# LAB-DEB429.net
KiCad netlist of a schematic drawn in EAGLE
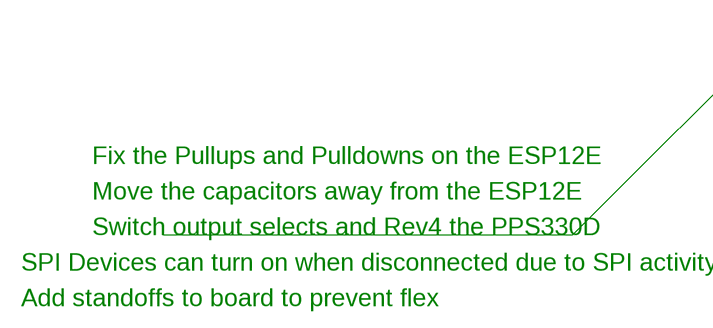
[diagram p0: schematic, sheet 1, part 1 of 2]
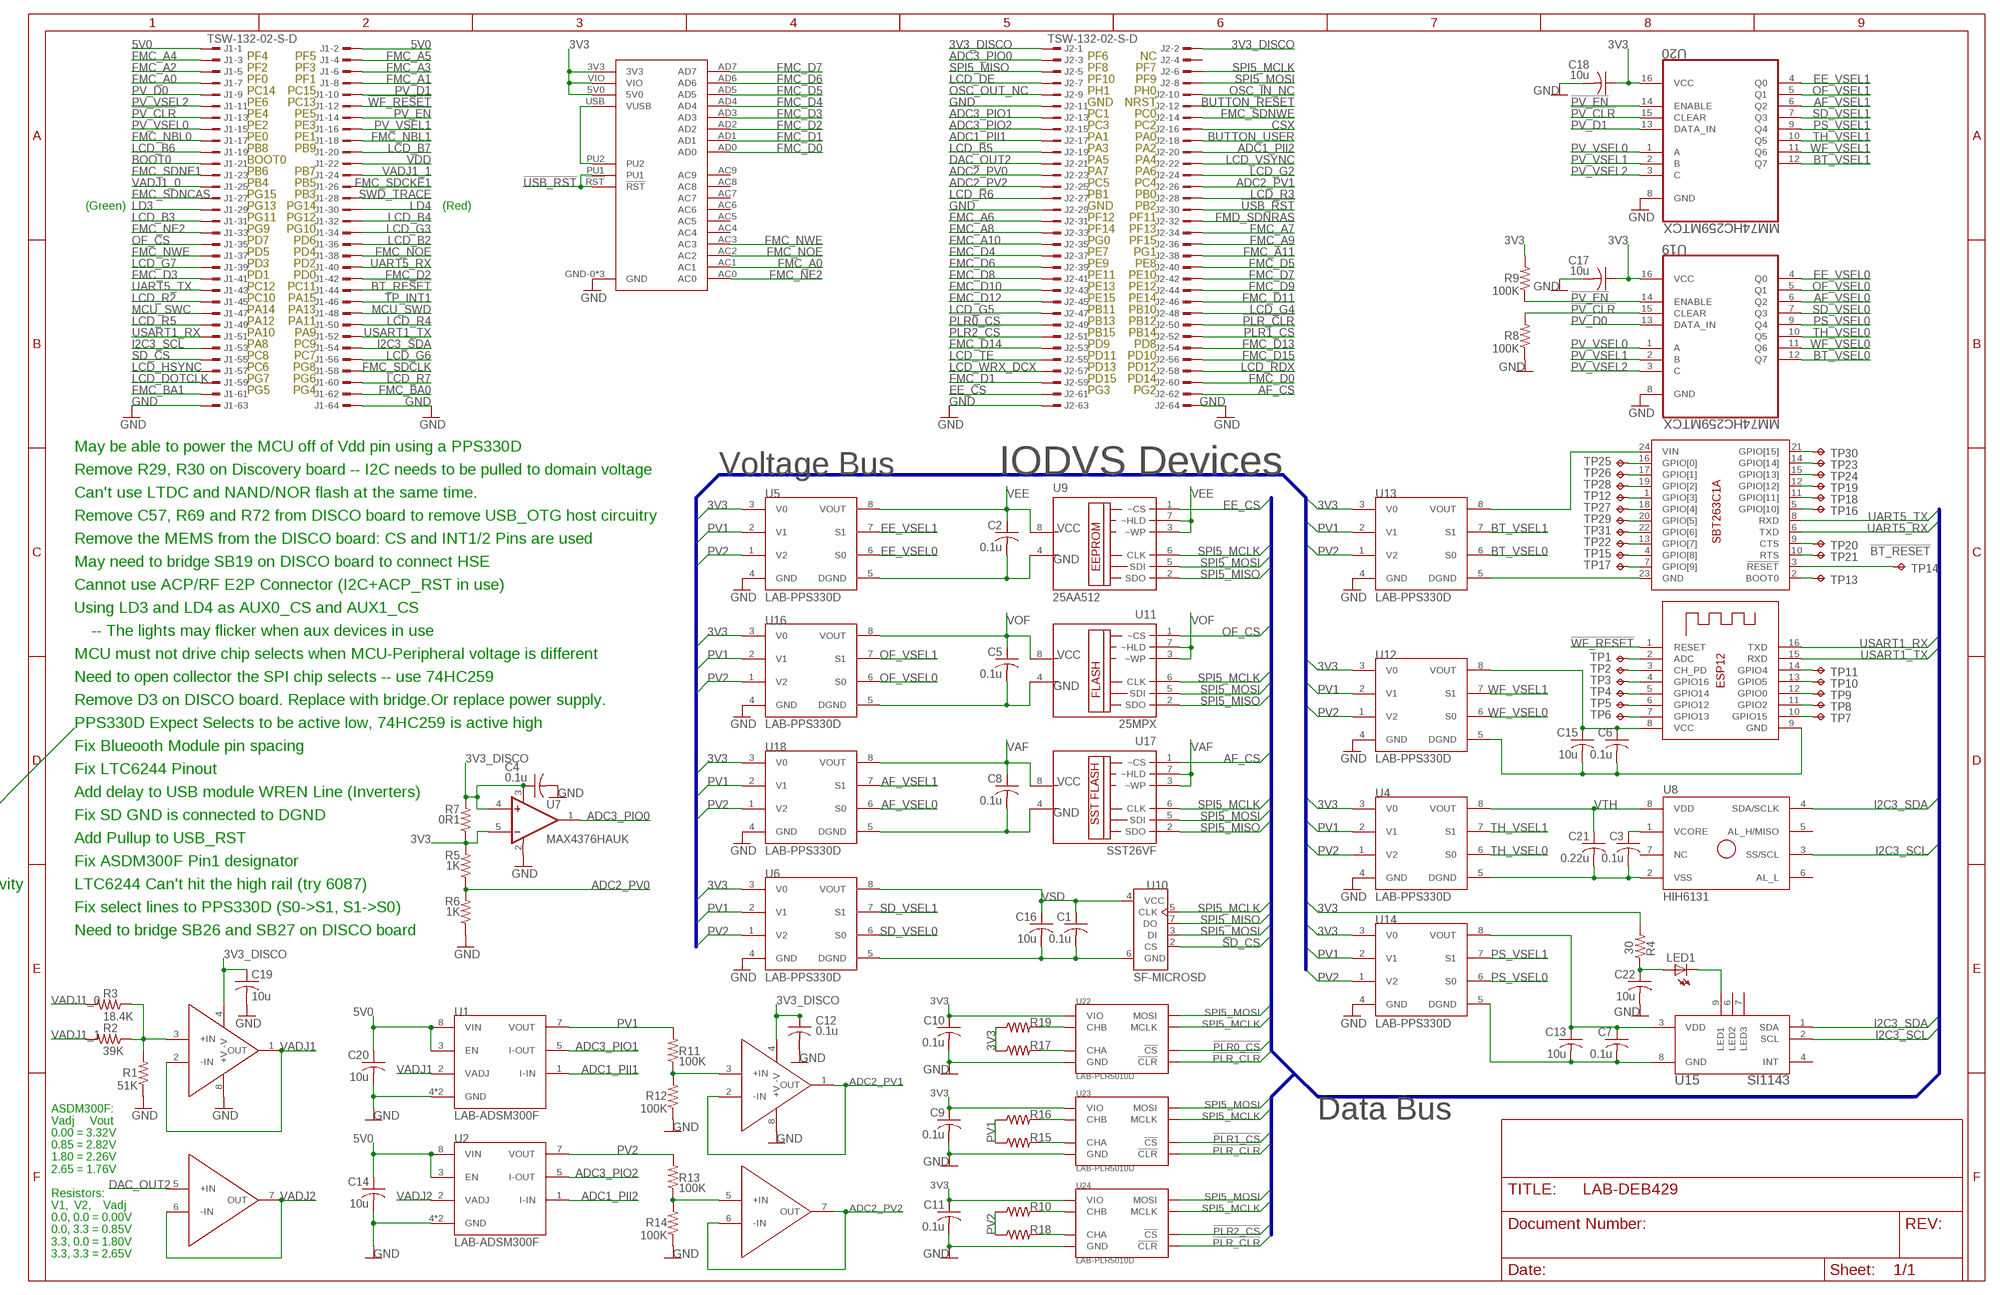
[diagram p1: schematic, sheet 1, part 2 of 2]

(export (version "E")
  (design (tool "Eeschema 10.0.6"))
  (components
    (comp (ref "C1")
      (value "0.1u")
      (footprint "eagle-import:C0603")
      (libsource (lib "eagle-import") (part "C-USC0603"))
    )
    (comp (ref "C2")
      (value "0.1u")
      (footprint "eagle-import:C0603")
      (libsource (lib "eagle-import") (part "C-USC0603"))
    )
    (comp (ref "C3")
      (value "0.1u")
      (footprint "eagle-import:C0603")
      (libsource (lib "eagle-import") (part "C-USC0603"))
    )
    (comp (ref "C4")
      (value "0.1u")
      (footprint "eagle-import:C0603")
      (libsource (lib "eagle-import") (part "C-USC0603"))
    )
    (comp (ref "C5")
      (value "0.1u")
      (footprint "eagle-import:C0603")
      (libsource (lib "eagle-import") (part "C-USC0603"))
    )
    (comp (ref "C6")
      (value "0.1u")
      (footprint "eagle-import:C0603")
      (libsource (lib "eagle-import") (part "C-USC0603"))
    )
    (comp (ref "C7")
      (value "0.1u")
      (footprint "eagle-import:C0603")
      (libsource (lib "eagle-import") (part "C-USC0603"))
    )
    (comp (ref "C8")
      (value "0.1u")
      (footprint "eagle-import:C0603")
      (libsource (lib "eagle-import") (part "C-USC0603"))
    )
    (comp (ref "C9")
      (value "0.1u")
      (footprint "eagle-import:C0603")
      (libsource (lib "eagle-import") (part "C-USC0603"))
    )
    (comp (ref "C10")
      (value "0.1u")
      (footprint "eagle-import:C0603")
      (libsource (lib "eagle-import") (part "C-USC0603"))
    )
    (comp (ref "C11")
      (value "0.1u")
      (footprint "eagle-import:C0603")
      (libsource (lib "eagle-import") (part "C-USC0603"))
    )
    (comp (ref "C12")
      (value "0.1u")
      (footprint "eagle-import:C0603")
      (libsource (lib "eagle-import") (part "C-USC0603"))
    )
    (comp (ref "C13")
      (value "10u")
      (footprint "eagle-import:C0603")
      (libsource (lib "eagle-import") (part "C-USC0603"))
    )
    (comp (ref "C14")
      (value "10u")
      (footprint "eagle-import:C0603")
      (libsource (lib "eagle-import") (part "C-USC0603"))
    )
    (comp (ref "C15")
      (value "10u")
      (footprint "eagle-import:C0603")
      (libsource (lib "eagle-import") (part "C-USC0603"))
    )
    (comp (ref "C16")
      (value "10u")
      (footprint "eagle-import:C0603")
      (libsource (lib "eagle-import") (part "C-USC0603"))
    )
    (comp (ref "C17")
      (value "10u")
      (footprint "eagle-import:C0603")
      (libsource (lib "eagle-import") (part "C-USC0603"))
    )
    (comp (ref "C18")
      (value "10u")
      (footprint "eagle-import:C0603")
      (libsource (lib "eagle-import") (part "C-USC0603"))
    )
    (comp (ref "C19")
      (value "10u")
      (footprint "eagle-import:C0603")
      (libsource (lib "eagle-import") (part "C-USC0603"))
    )
    (comp (ref "C20")
      (value "10u")
      (footprint "eagle-import:C0603")
      (libsource (lib "eagle-import") (part "C-USC0603"))
    )
    (comp (ref "C21")
      (value "0.22u")
      (footprint "eagle-import:C0603")
      (libsource (lib "eagle-import") (part "C-USC0603"))
    )
    (comp (ref "C22")
      (value "10u")
      (footprint "eagle-import:C0603")
      (libsource (lib "eagle-import") (part "C-USC0603"))
    )
    (comp (ref "J1")
      (value "TSW-132-02-S-D")
      (footprint "eagle-import:TSW-132-02-S-D")
      (libsource (lib "eagle-import") (part "TSW-132-02-S-D"))
    )
    (comp (ref "J2")
      (value "TSW-132-02-S-D")
      (footprint "eagle-import:TSW-132-02-S-D")
      (libsource (lib "eagle-import") (part "TSW-132-02-S-D"))
    )
    (comp (ref "LED1")
      (value "LEDCHIPLED_1206")
      (footprint "eagle-import:CHIPLED_1206")
      (libsource (lib "eagle-import") (part "LEDCHIPLED_1206"))
    )
    (comp (ref "R1")
      (value "51K")
      (footprint "eagle-import:R0603")
      (libsource (lib "eagle-import") (part "R-US_R0603"))
    )
    (comp (ref "R2")
      (value "39K")
      (footprint "eagle-import:R0603")
      (libsource (lib "eagle-import") (part "R-US_R0603"))
    )
    (comp (ref "R3")
      (value "18.4K")
      (footprint "eagle-import:R0603")
      (libsource (lib "eagle-import") (part "R-US_R0603"))
    )
    (comp (ref "R4")
      (value "30")
      (footprint "eagle-import:R0603")
      (libsource (lib "eagle-import") (part "R-US_R0603"))
    )
    (comp (ref "R5")
      (value "1K")
      (footprint "eagle-import:R0603")
      (libsource (lib "eagle-import") (part "R-US_R0603"))
    )
    (comp (ref "R6")
      (value "1K")
      (footprint "eagle-import:R0603")
      (libsource (lib "eagle-import") (part "R-US_R0603"))
    )
    (comp (ref "R7")
      (value "0R1")
      (footprint "eagle-import:R0603")
      (libsource (lib "eagle-import") (part "R-US_R0603"))
    )
    (comp (ref "R8")
      (value "100K")
      (footprint "eagle-import:R0603")
      (libsource (lib "eagle-import") (part "R-US_R0603"))
    )
    (comp (ref "R9")
      (value "100K")
      (footprint "eagle-import:R0603")
      (libsource (lib "eagle-import") (part "R-US_R0603"))
    )
    (comp (ref "R10")
      (value "R-US_0204/7")
      (footprint "eagle-import:0204_7")
      (libsource (lib "eagle-import") (part "R-US_0204/7"))
    )
    (comp (ref "R11")
      (value "100K")
      (footprint "eagle-import:R0603")
      (libsource (lib "eagle-import") (part "R-US_R0603"))
    )
    (comp (ref "R12")
      (value "100K")
      (footprint "eagle-import:R0603")
      (libsource (lib "eagle-import") (part "R-US_R0603"))
    )
    (comp (ref "R13")
      (value "100K")
      (footprint "eagle-import:R0603")
      (libsource (lib "eagle-import") (part "R-US_R0603"))
    )
    (comp (ref "R14")
      (value "100K")
      (footprint "eagle-import:R0603")
      (libsource (lib "eagle-import") (part "R-US_R0603"))
    )
    (comp (ref "R15")
      (value "R-US_0204/7")
      (footprint "eagle-import:0204_7")
      (libsource (lib "eagle-import") (part "R-US_0204/7"))
    )
    (comp (ref "R16")
      (value "R-US_0204/7")
      (footprint "eagle-import:0204_7")
      (libsource (lib "eagle-import") (part "R-US_0204/7"))
    )
    (comp (ref "R17")
      (value "R-US_0204/7")
      (footprint "eagle-import:0204_7")
      (libsource (lib "eagle-import") (part "R-US_0204/7"))
    )
    (comp (ref "R18")
      (value "R-US_0204/7")
      (footprint "eagle-import:0204_7")
      (libsource (lib "eagle-import") (part "R-US_0204/7"))
    )
    (comp (ref "R19")
      (value "R-US_0204/7")
      (footprint "eagle-import:0204_7")
      (libsource (lib "eagle-import") (part "R-US_0204/7"))
    )
    (comp (ref "TP1")
      (value "TPPAD1-13")
      (footprint "eagle-import:P1-13")
      (libsource (lib "eagle-import") (part "TPPAD1-13"))
    )
    (comp (ref "TP2")
      (value "TPPAD1-13")
      (footprint "eagle-import:P1-13")
      (libsource (lib "eagle-import") (part "TPPAD1-13"))
    )
    (comp (ref "TP3")
      (value "TPPAD1-13")
      (footprint "eagle-import:P1-13")
      (libsource (lib "eagle-import") (part "TPPAD1-13"))
    )
    (comp (ref "TP4")
      (value "TPPAD1-13")
      (footprint "eagle-import:P1-13")
      (libsource (lib "eagle-import") (part "TPPAD1-13"))
    )
    (comp (ref "TP5")
      (value "TPPAD1-13")
      (footprint "eagle-import:P1-13")
      (libsource (lib "eagle-import") (part "TPPAD1-13"))
    )
    (comp (ref "TP6")
      (value "TPPAD1-13")
      (footprint "eagle-import:P1-13")
      (libsource (lib "eagle-import") (part "TPPAD1-13"))
    )
    (comp (ref "TP7")
      (value "TPPAD1-13")
      (footprint "eagle-import:P1-13")
      (libsource (lib "eagle-import") (part "TPPAD1-13"))
    )
    (comp (ref "TP8")
      (value "TPPAD1-13")
      (footprint "eagle-import:P1-13")
      (libsource (lib "eagle-import") (part "TPPAD1-13"))
    )
    (comp (ref "TP9")
      (value "TPPAD1-13")
      (footprint "eagle-import:P1-13")
      (libsource (lib "eagle-import") (part "TPPAD1-13"))
    )
    (comp (ref "TP10")
      (value "TPPAD1-13")
      (footprint "eagle-import:P1-13")
      (libsource (lib "eagle-import") (part "TPPAD1-13"))
    )
    (comp (ref "TP11")
      (value "TPPAD1-13")
      (footprint "eagle-import:P1-13")
      (libsource (lib "eagle-import") (part "TPPAD1-13"))
    )
    (comp (ref "TP12")
      (value "TPPAD1-13")
      (footprint "eagle-import:P1-13")
      (libsource (lib "eagle-import") (part "TPPAD1-13"))
    )
    (comp (ref "TP13")
      (value "TPPAD1-13")
      (footprint "eagle-import:P1-13")
      (libsource (lib "eagle-import") (part "TPPAD1-13"))
    )
    (comp (ref "TP14")
      (value "TPPAD1-13")
      (footprint "eagle-import:P1-13")
      (libsource (lib "eagle-import") (part "TPPAD1-13"))
    )
    (comp (ref "TP15")
      (value "TPPAD1-13")
      (footprint "eagle-import:P1-13")
      (libsource (lib "eagle-import") (part "TPPAD1-13"))
    )
    (comp (ref "TP16")
      (value "TPPAD1-13")
      (footprint "eagle-import:P1-13")
      (libsource (lib "eagle-import") (part "TPPAD1-13"))
    )
    (comp (ref "TP17")
      (value "TPPAD1-13")
      (footprint "eagle-import:P1-13")
      (libsource (lib "eagle-import") (part "TPPAD1-13"))
    )
    (comp (ref "TP18")
      (value "TPPAD1-13")
      (footprint "eagle-import:P1-13")
      (libsource (lib "eagle-import") (part "TPPAD1-13"))
    )
    (comp (ref "TP19")
      (value "TPPAD1-13")
      (footprint "eagle-import:P1-13")
      (libsource (lib "eagle-import") (part "TPPAD1-13"))
    )
    (comp (ref "TP20")
      (value "TPPAD1-13")
      (footprint "eagle-import:P1-13")
      (libsource (lib "eagle-import") (part "TPPAD1-13"))
    )
    (comp (ref "TP21")
      (value "TPPAD1-13")
      (footprint "eagle-import:P1-13")
      (libsource (lib "eagle-import") (part "TPPAD1-13"))
    )
    (comp (ref "TP22")
      (value "TPPAD1-13")
      (footprint "eagle-import:P1-13")
      (libsource (lib "eagle-import") (part "TPPAD1-13"))
    )
    (comp (ref "TP23")
      (value "TPPAD1-13")
      (footprint "eagle-import:P1-13")
      (libsource (lib "eagle-import") (part "TPPAD1-13"))
    )
    (comp (ref "TP24")
      (value "TPPAD1-13")
      (footprint "eagle-import:P1-13")
      (libsource (lib "eagle-import") (part "TPPAD1-13"))
    )
    (comp (ref "TP25")
      (value "TPPAD1-13")
      (footprint "eagle-import:P1-13")
      (libsource (lib "eagle-import") (part "TPPAD1-13"))
    )
    (comp (ref "TP26")
      (value "TPPAD1-13")
      (footprint "eagle-import:P1-13")
      (libsource (lib "eagle-import") (part "TPPAD1-13"))
    )
    (comp (ref "TP27")
      (value "TPPAD1-13")
      (footprint "eagle-import:P1-13")
      (libsource (lib "eagle-import") (part "TPPAD1-13"))
    )
    (comp (ref "TP28")
      (value "TPPAD1-13")
      (footprint "eagle-import:P1-13")
      (libsource (lib "eagle-import") (part "TPPAD1-13"))
    )
    (comp (ref "TP29")
      (value "TPPAD1-13")
      (footprint "eagle-import:P1-13")
      (libsource (lib "eagle-import") (part "TPPAD1-13"))
    )
    (comp (ref "TP30")
      (value "TPPAD1-13")
      (footprint "eagle-import:P1-13")
      (libsource (lib "eagle-import") (part "TPPAD1-13"))
    )
    (comp (ref "TP31")
      (value "TPPAD1-13")
      (footprint "eagle-import:P1-13")
      (libsource (lib "eagle-import") (part "TPPAD1-13"))
    )
    (comp (ref "U1")
      (value "LAB-ADSM300F")
      (footprint "eagle-import:LAB-ASDM300F")
      (libsource (lib "eagle-import") (part "LAB-ADSM300F"))
    )
    (comp (ref "U2")
      (value "LAB-ADSM300F")
      (footprint "eagle-import:LAB-ASDM300F")
      (libsource (lib "eagle-import") (part "LAB-ADSM300F"))
    )
    (comp (ref "U3")
      (value "LTC6244")
      (footprint "eagle-import:MSOP8")
      (libsource (lib "eagle-import") (part "LTC6244"))
    )
    (comp (ref "U4")
      (value "LAB-PPS330D")
      (footprint "eagle-import:LAB-PPS330D")
      (libsource (lib "eagle-import") (part "LAB-PPS330D"))
    )
    (comp (ref "U5")
      (value "LAB-PPS330D")
      (footprint "eagle-import:LAB-PPS330D")
      (libsource (lib "eagle-import") (part "LAB-PPS330D"))
    )
    (comp (ref "U6")
      (value "LAB-PPS330D")
      (footprint "eagle-import:LAB-PPS330D")
      (libsource (lib "eagle-import") (part "LAB-PPS330D"))
    )
    (comp (ref "U7")
      (value "MAX4376HAUK")
      (footprint "eagle-import:SOT23-5")
      (libsource (lib "eagle-import") (part "MAX4376"))
    )
    (comp (ref "U8")
      (value "HIH6131")
      (footprint "eagle-import:SO-08M")
      (libsource (lib "eagle-import") (part "HIH6131"))
    )
    (comp (ref "U9")
      (value "25AA512")
      (footprint "eagle-import:SO-08M")
      (libsource (lib "eagle-import") (part "25AA512"))
    )
    (comp (ref "U10")
      (value "SF-MICROSD")
      (footprint "eagle-import:MICROSD")
      (libsource (lib "eagle-import") (part "SF-MICROSD"))
    )
    (comp (ref "U11")
      (value "25MPX")
      (footprint "eagle-import:SO-08M")
      (libsource (lib "eagle-import") (part "25MPX"))
    )
    (comp (ref "U12")
      (value "LAB-PPS330D")
      (footprint "eagle-import:LAB-PPS330D")
      (libsource (lib "eagle-import") (part "LAB-PPS330D"))
    )
    (comp (ref "U13")
      (value "LAB-PPS330D")
      (footprint "eagle-import:LAB-PPS330D")
      (libsource (lib "eagle-import") (part "LAB-PPS330D"))
    )
    (comp (ref "U14")
      (value "LAB-PPS330D")
      (footprint "eagle-import:LAB-PPS330D")
      (libsource (lib "eagle-import") (part "LAB-PPS330D"))
    )
    (comp (ref "U15")
      (value "SI1143")
      (footprint "eagle-import:QFN10")
      (libsource (lib "eagle-import") (part "SI1143"))
    )
    (comp (ref "U16")
      (value "LAB-PPS330D")
      (footprint "eagle-import:LAB-PPS330D")
      (libsource (lib "eagle-import") (part "LAB-PPS330D"))
    )
    (comp (ref "U17")
      (value "SST26VF")
      (footprint "eagle-import:SO-08M")
      (libsource (lib "eagle-import") (part "SST26VF"))
    )
    (comp (ref "U18")
      (value "LAB-PPS330D")
      (footprint "eagle-import:LAB-PPS330D")
      (libsource (lib "eagle-import") (part "LAB-PPS330D"))
    )
    (comp (ref "U19")
      (value "MM74HC259MTCX")
      (footprint "eagle-import:SOP65P640X90-16N")
      (libsource (lib "eagle-import") (part "MM74HC259MTCX"))
    )
    (comp (ref "U20")
      (value "MM74HC259MTCX")
      (footprint "eagle-import:SOP65P640X90-16N")
      (libsource (lib "eagle-import") (part "MM74HC259MTCX"))
    )
    (comp (ref "U21")
      (value "LTC6244")
      (footprint "eagle-import:MSOP8")
      (libsource (lib "eagle-import") (part "LTC6244"))
    )
    (comp (ref "U22")
      (value "LAB-PLR5010D")
      (footprint "eagle-import:LAB-PLR5010D")
      (libsource (lib "eagle-import") (part "LAB-PLR5010D"))
    )
    (comp (ref "U23")
      (value "LAB-PLR5010D")
      (footprint "eagle-import:LAB-PLR5010D")
      (libsource (lib "eagle-import") (part "LAB-PLR5010D"))
    )
    (comp (ref "U24")
      (value "LAB-PLR5010D")
      (footprint "eagle-import:LAB-PLR5010D")
      (libsource (lib "eagle-import") (part "LAB-PLR5010D"))
    )
    (comp (ref "U25")
      (value "ESP-12")
      (footprint "eagle-import:ESP-12")
      (libsource (lib "eagle-import") (part "ESP-12"))
    )
    (comp (ref "U26")
      (value "SPBT2632C1A")
      (footprint "eagle-import:SPBT2632C1A")
      (libsource (lib "eagle-import") (part "SPBT2632C1A"))
    )
    (comp (ref "U27")
      (value "UM232H")
      (footprint "eagle-import:UM232H")
      (libsource (lib "eagle-import") (part "UM232H"))
    )
  )
  (nets
    (net (code "1") (name "/3V3") (class "Default")
      (node (ref "C10") (pin "1") (pinfunction "1_1") (pintype "passive"))
      (node (ref "C11") (pin "1") (pinfunction "1_1") (pintype "passive"))
      (node (ref "C17") (pin "1") (pinfunction "1_1") (pintype "passive"))
      (node (ref "C18") (pin "1") (pinfunction "1_1") (pintype "passive"))
      (node (ref "C9") (pin "1") (pinfunction "1_1") (pintype "passive"))
      (node (ref "R17") (pin "1") (pinfunction "1_1") (pintype "passive"))
      (node (ref "R19") (pin "1") (pinfunction "1_1") (pintype "passive"))
      (node (ref "R4") (pin "2") (pinfunction "2_2") (pintype "passive"))
      (node (ref "R5") (pin "2") (pinfunction "2_2") (pintype "passive"))
      (node (ref "R7") (pin "1") (pinfunction "1_1") (pintype "passive"))
      (node (ref "R9") (pin "2") (pinfunction "2_2") (pintype "passive"))
      (node (ref "U12") (pin "3") (pinfunction "V0_3") (pintype "power_in"))
      (node (ref "U13") (pin "3") (pinfunction "V0_3") (pintype "power_in"))
      (node (ref "U14") (pin "3") (pinfunction "V0_3") (pintype "power_in"))
      (node (ref "U16") (pin "3") (pinfunction "V0_3") (pintype "power_in"))
      (node (ref "U18") (pin "3") (pinfunction "V0_3") (pintype "power_in"))
      (node (ref "U19") (pin "16") (pinfunction "VCC_16") (pintype "power_in"))
      (node (ref "U20") (pin "16") (pinfunction "VCC_16") (pintype "power_in"))
      (node (ref "U22") (pin "VDD") (pinfunction "VIO_VDD") (pintype "power_in"))
      (node (ref "U23") (pin "VDD") (pinfunction "VIO_VDD") (pintype "power_in"))
      (node (ref "U24") (pin "VDD") (pinfunction "VIO_VDD") (pintype "power_in"))
      (node (ref "U27") (pin "3V3") (pinfunction "3V3_3V3") (pintype "power_in"))
      (node (ref "U27") (pin "5V0") (pinfunction "5V0_5V0") (pintype "bidirectional"))
      (node (ref "U27") (pin "VIO") (pinfunction "VIO_VIO") (pintype "power_in"))
      (node (ref "U4") (pin "3") (pinfunction "V0_3") (pintype "power_in"))
      (node (ref "U5") (pin "3") (pinfunction "V0_3") (pintype "power_in"))
      (node (ref "U6") (pin "3") (pinfunction "V0_3") (pintype "power_in"))
      (node (ref "U7") (pin "5") (pinfunction "-IN_5") (pintype "input"))
    )
    (net (code "2") (name "/3V3_DISCO") (class "Default")
      (node (ref "C12") (pin "1") (pinfunction "1_1") (pintype "passive"))
      (node (ref "C19") (pin "1") (pinfunction "1_1") (pintype "passive"))
      (node (ref "C4") (pin "1") (pinfunction "1_1") (pintype "passive"))
      (node (ref "J2") (pin "1") (pinfunction "1_1") (pintype "passive"))
      (node (ref "J2") (pin "2") (pinfunction "1_2") (pintype "passive"))
      (node (ref "R7") (pin "2") (pinfunction "2_2") (pintype "passive"))
      (node (ref "U21") (pin "4") (pinfunction "-V_4") (pintype "bidirectional"))
      (node (ref "U3") (pin "4") (pinfunction "-V_4") (pintype "bidirectional"))
      (node (ref "U7") (pin "3") (pinfunction "V+_3") (pintype "power_in"))
      (node (ref "U7") (pin "4") (pinfunction "+IN_4") (pintype "input"))
    )
    (net (code "3") (name "/5V0") (class "Default")
      (node (ref "C14") (pin "1") (pinfunction "1_1") (pintype "passive"))
      (node (ref "C20") (pin "1") (pinfunction "1_1") (pintype "passive"))
      (node (ref "J1") (pin "1") (pinfunction "1_1") (pintype "passive"))
      (node (ref "J1") (pin "2") (pinfunction "1_2") (pintype "passive"))
      (node (ref "U1") (pin "3") (pinfunction "EN_3") (pintype "input"))
      (node (ref "U1") (pin "8") (pinfunction "VIN_8") (pintype "power_in"))
      (node (ref "U2") (pin "3") (pinfunction "EN_3") (pintype "input"))
      (node (ref "U2") (pin "8") (pinfunction "VIN_8") (pintype "power_in"))
    )
    (net (code "4") (name "/ADC1_PII1") (class "Default")
      (node (ref "J2") (pin "17") (pinfunction "1_17") (pintype "passive"))
      (node (ref "U1") (pin "1") (pinfunction "I-IN_1") (pintype "output"))
    )
    (net (code "5") (name "/ADC1_PII2") (class "Default")
      (node (ref "J2") (pin "20") (pinfunction "1_20") (pintype "passive"))
      (node (ref "U2") (pin "1") (pinfunction "I-IN_1") (pintype "output"))
    )
    (net (code "6") (name "/ADC2_PV0") (class "Default")
      (node (ref "J2") (pin "23") (pinfunction "1_23") (pintype "passive"))
      (node (ref "R5") (pin "1") (pinfunction "1_1") (pintype "passive"))
      (node (ref "R6") (pin "2") (pinfunction "2_2") (pintype "passive"))
    )
    (net (code "7") (name "/ADC2_PV1") (class "Default")
      (node (ref "J2") (pin "26") (pinfunction "1_26") (pintype "passive"))
      (node (ref "U21") (pin "1") (pinfunction "OUT_1") (pintype "bidirectional"))
      (node (ref "U21") (pin "2") (pinfunction "-IN_2") (pintype "bidirectional"))
    )
    (net (code "8") (name "/ADC2_PV2") (class "Default")
      (node (ref "J2") (pin "25") (pinfunction "1_25") (pintype "passive"))
      (node (ref "U21") (pin "6") (pinfunction "-IN_6") (pintype "bidirectional"))
      (node (ref "U21") (pin "7") (pinfunction "OUT_7") (pintype "bidirectional"))
    )
    (net (code "9") (name "/ADC3_PIO0") (class "Default")
      (node (ref "J2") (pin "3") (pinfunction "1_3") (pintype "passive"))
      (node (ref "U7") (pin "1") (pinfunction "OUT_1") (pintype "output"))
    )
    (net (code "10") (name "/ADC3_PIO1") (class "Default")
      (node (ref "J2") (pin "13") (pinfunction "1_13") (pintype "passive"))
      (node (ref "U1") (pin "5") (pinfunction "I-OUT_5") (pintype "output"))
    )
    (net (code "11") (name "/ADC3_PIO2") (class "Default")
      (node (ref "J2") (pin "15") (pinfunction "1_15") (pintype "passive"))
      (node (ref "U2") (pin "5") (pinfunction "I-OUT_5") (pintype "output"))
    )
    (net (code "12") (name "/AF_CS") (class "Default")
      (node (ref "J2") (pin "62") (pinfunction "1_62") (pintype "passive"))
      (node (ref "U17") (pin "1") (pinfunction "~{CS}_1") (pintype "input"))
    )
    (net (code "13") (name "/AF_VSEL0") (class "Default")
      (node (ref "U18") (pin "6") (pinfunction "S0_6") (pintype "input"))
      (node (ref "U19") (pin "6") (pinfunction "Q2_6") (pintype "output"))
    )
    (net (code "14") (name "/AF_VSEL1") (class "Default")
      (node (ref "U18") (pin "7") (pinfunction "S1_7") (pintype "input"))
      (node (ref "U20") (pin "6") (pinfunction "Q2_6") (pintype "output"))
    )
    (net (code "15") (name "/BOOT0") (class "Default")
      (node (ref "J1") (pin "21") (pinfunction "1_21") (pintype "passive"))
    )
    (net (code "16") (name "/BT_VSEL0") (class "Default")
      (node (ref "U13") (pin "6") (pinfunction "S0_6") (pintype "input"))
      (node (ref "U19") (pin "12") (pinfunction "Q7_12") (pintype "output"))
    )
    (net (code "17") (name "/BT_VSEL1") (class "Default")
      (node (ref "U13") (pin "7") (pinfunction "S1_7") (pintype "input"))
      (node (ref "U20") (pin "12") (pinfunction "Q7_12") (pintype "output"))
    )
    (net (code "18") (name "/BUTTON_RESET") (class "Default")
      (node (ref "J2") (pin "12") (pinfunction "1_12") (pintype "passive"))
    )
    (net (code "19") (name "/BUTTON_USER") (class "Default")
      (node (ref "J2") (pin "18") (pinfunction "1_18") (pintype "passive"))
    )
    (net (code "20") (name "/CSX") (class "Default")
      (node (ref "J2") (pin "16") (pinfunction "1_16") (pintype "passive"))
    )
    (net (code "21") (name "/DAC_OUT2") (class "Default")
      (node (ref "J2") (pin "21") (pinfunction "1_21") (pintype "passive"))
      (node (ref "U3") (pin "5") (pinfunction "+IN_5") (pintype "bidirectional"))
    )
    (net (code "22") (name "/EE_CS") (class "Default")
      (node (ref "J2") (pin "61") (pinfunction "1_61") (pintype "passive"))
      (node (ref "U9") (pin "1") (pinfunction "~{CS}_1") (pintype "input"))
    )
    (net (code "23") (name "/EE_VSEL0") (class "Default")
      (node (ref "U19") (pin "4") (pinfunction "Q0_4") (pintype "output"))
      (node (ref "U5") (pin "6") (pinfunction "S0_6") (pintype "input"))
    )
    (net (code "24") (name "/EE_VSEL1") (class "Default")
      (node (ref "U20") (pin "4") (pinfunction "Q0_4") (pintype "output"))
      (node (ref "U5") (pin "7") (pinfunction "S1_7") (pintype "input"))
    )
    (net (code "25") (name "/FMC_A0") (class "Default")
      (node (ref "J1") (pin "7") (pinfunction "1_7") (pintype "passive"))
      (node (ref "U27") (pin "AC1") (pinfunction "AC1_AC1") (pintype "bidirectional"))
    )
    (net (code "26") (name "/FMC_A1") (class "Default")
      (node (ref "J1") (pin "8") (pinfunction "1_8") (pintype "passive"))
    )
    (net (code "27") (name "/FMC_A2") (class "Default")
      (node (ref "J1") (pin "5") (pinfunction "1_5") (pintype "passive"))
    )
    (net (code "28") (name "/FMC_A3") (class "Default")
      (node (ref "J1") (pin "6") (pinfunction "1_6") (pintype "passive"))
    )
    (net (code "29") (name "/FMC_A4") (class "Default")
      (node (ref "J1") (pin "3") (pinfunction "1_3") (pintype "passive"))
    )
    (net (code "30") (name "/FMC_A5") (class "Default")
      (node (ref "J1") (pin "4") (pinfunction "1_4") (pintype "passive"))
    )
    (net (code "31") (name "/FMC_A6") (class "Default")
      (node (ref "J2") (pin "31") (pinfunction "1_31") (pintype "passive"))
    )
    (net (code "32") (name "/FMC_A7") (class "Default")
      (node (ref "J2") (pin "34") (pinfunction "1_34") (pintype "passive"))
    )
    (net (code "33") (name "/FMC_A8") (class "Default")
      (node (ref "J2") (pin "33") (pinfunction "1_33") (pintype "passive"))
    )
    (net (code "34") (name "/FMC_A9") (class "Default")
      (node (ref "J2") (pin "36") (pinfunction "1_36") (pintype "passive"))
    )
    (net (code "35") (name "/FMC_A10") (class "Default")
      (node (ref "J2") (pin "35") (pinfunction "1_35") (pintype "passive"))
    )
    (net (code "36") (name "/FMC_A11") (class "Default")
      (node (ref "J2") (pin "38") (pinfunction "1_38") (pintype "passive"))
    )
    (net (code "37") (name "/FMC_BA0") (class "Default")
      (node (ref "J1") (pin "62") (pinfunction "1_62") (pintype "passive"))
    )
    (net (code "38") (name "/FMC_BA1") (class "Default")
      (node (ref "J1") (pin "61") (pinfunction "1_61") (pintype "passive"))
    )
    (net (code "39") (name "/FMC_D0") (class "Default")
      (node (ref "J2") (pin "60") (pinfunction "1_60") (pintype "passive"))
      (node (ref "U27") (pin "AD0") (pinfunction "AD0_AD0") (pintype "bidirectional"))
    )
    (net (code "40") (name "/FMC_D1") (class "Default")
      (node (ref "J2") (pin "59") (pinfunction "1_59") (pintype "passive"))
      (node (ref "U27") (pin "AD1") (pinfunction "AD1_AD1") (pintype "bidirectional"))
    )
    (net (code "41") (name "/FMC_D2") (class "Default")
      (node (ref "J1") (pin "42") (pinfunction "1_42") (pintype "passive"))
      (node (ref "U27") (pin "AD2") (pinfunction "AD2_AD2") (pintype "bidirectional"))
    )
    (net (code "42") (name "/FMC_D3") (class "Default")
      (node (ref "J1") (pin "41") (pinfunction "1_41") (pintype "passive"))
      (node (ref "U27") (pin "AD3") (pinfunction "AD3_AD3") (pintype "bidirectional"))
    )
    (net (code "43") (name "/FMC_D4") (class "Default")
      (node (ref "J2") (pin "37") (pinfunction "1_37") (pintype "passive"))
      (node (ref "U27") (pin "AD4") (pinfunction "AD4_AD4") (pintype "bidirectional"))
    )
    (net (code "44") (name "/FMC_D5") (class "Default")
      (node (ref "J2") (pin "40") (pinfunction "1_40") (pintype "passive"))
      (node (ref "U27") (pin "AD5") (pinfunction "AD5_AD5") (pintype "bidirectional"))
    )
    (net (code "45") (name "/FMC_D6") (class "Default")
      (node (ref "J2") (pin "39") (pinfunction "1_39") (pintype "passive"))
      (node (ref "U27") (pin "AD6") (pinfunction "AD6_AD6") (pintype "bidirectional"))
    )
    (net (code "46") (name "/FMC_D7") (class "Default")
      (node (ref "J2") (pin "42") (pinfunction "1_42") (pintype "passive"))
      (node (ref "U27") (pin "AD7") (pinfunction "AD7_AD7") (pintype "bidirectional"))
    )
    (net (code "47") (name "/FMC_D8") (class "Default")
      (node (ref "J2") (pin "41") (pinfunction "1_41") (pintype "passive"))
    )
    (net (code "48") (name "/FMC_D9") (class "Default")
      (node (ref "J2") (pin "44") (pinfunction "1_44") (pintype "passive"))
    )
    (net (code "49") (name "/FMC_D10") (class "Default")
      (node (ref "J2") (pin "43") (pinfunction "1_43") (pintype "passive"))
    )
    (net (code "50") (name "/FMC_D11") (class "Default")
      (node (ref "J2") (pin "46") (pinfunction "1_46") (pintype "passive"))
    )
    (net (code "51") (name "/FMC_D12") (class "Default")
      (node (ref "J2") (pin "45") (pinfunction "1_45") (pintype "passive"))
    )
    (net (code "52") (name "/FMC_D13") (class "Default")
      (node (ref "J2") (pin "54") (pinfunction "1_54") (pintype "passive"))
    )
    (net (code "53") (name "/FMC_D14") (class "Default")
      (node (ref "J2") (pin "53") (pinfunction "1_53") (pintype "passive"))
    )
    (net (code "54") (name "/FMC_D15") (class "Default")
      (node (ref "J2") (pin "56") (pinfunction "1_56") (pintype "passive"))
    )
    (net (code "55") (name "/FMC_NBL0") (class "Default")
      (node (ref "J1") (pin "17") (pinfunction "1_17") (pintype "passive"))
    )
    (net (code "56") (name "/FMC_NBL1") (class "Default")
      (node (ref "J1") (pin "18") (pinfunction "1_18") (pintype "passive"))
    )
    (net (code "57") (name "/FMC_NE2") (class "Default")
      (node (ref "J1") (pin "33") (pinfunction "1_33") (pintype "passive"))
      (node (ref "U27") (pin "AC0") (pinfunction "AC0_AC0") (pintype "bidirectional"))
    )
    (net (code "58") (name "/FMC_NOE") (class "Default")
      (node (ref "J1") (pin "38") (pinfunction "1_38") (pintype "passive"))
      (node (ref "U27") (pin "AC2") (pinfunction "AC2_AC2") (pintype "bidirectional"))
    )
    (net (code "59") (name "/FMC_NWE") (class "Default")
      (node (ref "J1") (pin "37") (pinfunction "1_37") (pintype "passive"))
      (node (ref "U27") (pin "AC3") (pinfunction "AC3_AC3") (pintype "bidirectional"))
    )
    (net (code "60") (name "/FMC_SDCKE1") (class "Default")
      (node (ref "J1") (pin "26") (pinfunction "1_26") (pintype "passive"))
    )
    (net (code "61") (name "/FMC_SDCLK") (class "Default")
      (node (ref "J1") (pin "58") (pinfunction "1_58") (pintype "passive"))
    )
    (net (code "62") (name "/FMC_SDNCAS") (class "Default")
      (node (ref "J1") (pin "27") (pinfunction "1_27") (pintype "passive"))
    )
    (net (code "63") (name "/FMC_SDNE1") (class "Default")
      (node (ref "J1") (pin "23") (pinfunction "1_23") (pintype "passive"))
    )
    (net (code "64") (name "/FMC_SDNWE") (class "Default")
      (node (ref "J2") (pin "14") (pinfunction "1_14") (pintype "passive"))
    )
    (net (code "65") (name "/FMD_SDNRAS") (class "Default")
      (node (ref "J2") (pin "32") (pinfunction "1_32") (pintype "passive"))
    )
    (net (code "66") (name "/I2C3_SCL") (class "Default")
      (node (ref "J1") (pin "53") (pinfunction "1_53") (pintype "passive"))
      (node (ref "U15") (pin "2") (pinfunction "SCL_2") (pintype "input"))
      (node (ref "U8") (pin "3") (pinfunction "SS/SCL_3") (pintype "bidirectional"))
    )
    (net (code "67") (name "/I2C3_SDA") (class "Default")
      (node (ref "J1") (pin "54") (pinfunction "1_54") (pintype "passive"))
      (node (ref "U15") (pin "1") (pinfunction "SDA_1") (pintype "passive"))
      (node (ref "U8") (pin "4") (pinfunction "SDA/SCLK_4") (pintype "bidirectional"))
    )
    (net (code "68") (name "/LCD_B2") (class "Default")
      (node (ref "J1") (pin "36") (pinfunction "1_36") (pintype "passive"))
    )
    (net (code "69") (name "/LCD_B3") (class "Default")
      (node (ref "J1") (pin "31") (pinfunction "1_31") (pintype "passive"))
    )
    (net (code "70") (name "/LCD_B4") (class "Default")
      (node (ref "J1") (pin "32") (pinfunction "1_32") (pintype "passive"))
    )
    (net (code "71") (name "/LCD_B5") (class "Default")
      (node (ref "J2") (pin "19") (pinfunction "1_19") (pintype "passive"))
    )
    (net (code "72") (name "/LCD_B6") (class "Default")
      (node (ref "J1") (pin "19") (pinfunction "1_19") (pintype "passive"))
    )
    (net (code "73") (name "/LCD_B7") (class "Default")
      (node (ref "J1") (pin "20") (pinfunction "1_20") (pintype "passive"))
    )
    (net (code "74") (name "/LCD_DE") (class "Default")
      (node (ref "J2") (pin "7") (pinfunction "1_7") (pintype "passive"))
    )
    (net (code "75") (name "/LCD_DOTCLK") (class "Default")
      (node (ref "J1") (pin "59") (pinfunction "1_59") (pintype "passive"))
    )
    (net (code "76") (name "/LCD_G2") (class "Default")
      (node (ref "J2") (pin "24") (pinfunction "1_24") (pintype "passive"))
    )
    (net (code "77") (name "/LCD_G3") (class "Default")
      (node (ref "J1") (pin "34") (pinfunction "1_34") (pintype "passive"))
    )
    (net (code "78") (name "/LCD_G4") (class "Default")
      (node (ref "J2") (pin "48") (pinfunction "1_48") (pintype "passive"))
    )
    (net (code "79") (name "/LCD_G5") (class "Default")
      (node (ref "J2") (pin "47") (pinfunction "1_47") (pintype "passive"))
    )
    (net (code "80") (name "/LCD_G6") (class "Default")
      (node (ref "J1") (pin "56") (pinfunction "1_56") (pintype "passive"))
    )
    (net (code "81") (name "/LCD_G7") (class "Default")
      (node (ref "J1") (pin "39") (pinfunction "1_39") (pintype "passive"))
    )
    (net (code "82") (name "/LCD_HSYNC") (class "Default")
      (node (ref "J1") (pin "57") (pinfunction "1_57") (pintype "passive"))
    )
    (net (code "83") (name "/LCD_R2") (class "Default")
      (node (ref "J1") (pin "45") (pinfunction "1_45") (pintype "passive"))
    )
    (net (code "84") (name "/LCD_R3") (class "Default")
      (node (ref "J2") (pin "28") (pinfunction "1_28") (pintype "passive"))
    )
    (net (code "85") (name "/LCD_R4") (class "Default")
      (node (ref "J1") (pin "50") (pinfunction "1_50") (pintype "passive"))
    )
    (net (code "86") (name "/LCD_R5") (class "Default")
      (node (ref "J1") (pin "49") (pinfunction "1_49") (pintype "passive"))
    )
    (net (code "87") (name "/LCD_R6") (class "Default")
      (node (ref "J2") (pin "27") (pinfunction "1_27") (pintype "passive"))
    )
    (net (code "88") (name "/LCD_R7") (class "Default")
      (node (ref "J1") (pin "60") (pinfunction "1_60") (pintype "passive"))
    )
    (net (code "89") (name "/LCD_RDX") (class "Default")
      (node (ref "J2") (pin "58") (pinfunction "1_58") (pintype "passive"))
    )
    (net (code "90") (name "/LCD_TE") (class "Default")
      (node (ref "J2") (pin "55") (pinfunction "1_55") (pintype "passive"))
    )
    (net (code "91") (name "/LCD_VSYNC") (class "Default")
      (node (ref "J2") (pin "22") (pinfunction "1_22") (pintype "passive"))
    )
    (net (code "92") (name "/LCD_WRX_DCX") (class "Default")
      (node (ref "J2") (pin "57") (pinfunction "1_57") (pintype "passive"))
    )
    (net (code "93") (name "/LD3") (class "Default")
      (node (ref "J1") (pin "29") (pinfunction "1_29") (pintype "passive"))
    )
    (net (code "94") (name "/LD4") (class "Default")
      (node (ref "J1") (pin "30") (pinfunction "1_30") (pintype "passive"))
    )
    (net (code "95") (name "/MCU_SWC") (class "Default")
      (node (ref "J1") (pin "47") (pinfunction "1_47") (pintype "passive"))
    )
    (net (code "96") (name "/MCU_SWD") (class "Default")
      (node (ref "J1") (pin "48") (pinfunction "1_48") (pintype "passive"))
    )
    (net (code "97") (name "/OF_CS") (class "Default")
      (node (ref "J1") (pin "35") (pinfunction "1_35") (pintype "passive"))
      (node (ref "U11") (pin "1") (pinfunction "~{CS}_1") (pintype "input"))
    )
    (net (code "98") (name "/OF_VSEL0") (class "Default")
      (node (ref "U16") (pin "6") (pinfunction "S0_6") (pintype "input"))
      (node (ref "U19") (pin "5") (pinfunction "Q1_5") (pintype "output"))
    )
    (net (code "99") (name "/OF_VSEL1") (class "Default")
      (node (ref "U16") (pin "7") (pinfunction "S1_7") (pintype "input"))
      (node (ref "U20") (pin "5") (pinfunction "Q1_5") (pintype "output"))
    )
    (net (code "100") (name "/OSC_IN_NC") (class "Default")
      (node (ref "J2") (pin "10") (pinfunction "1_10") (pintype "passive"))
    )
    (net (code "101") (name "/OSC_OUT_NC") (class "Default")
      (node (ref "J2") (pin "9") (pinfunction "1_9") (pintype "passive"))
    )
    (net (code "102") (name "/PS_VSEL0") (class "Default")
      (node (ref "U14") (pin "6") (pinfunction "S0_6") (pintype "input"))
      (node (ref "U19") (pin "9") (pinfunction "Q4_9") (pintype "output"))
    )
    (net (code "103") (name "/PS_VSEL1") (class "Default")
      (node (ref "U14") (pin "7") (pinfunction "S1_7") (pintype "input"))
      (node (ref "U20") (pin "9") (pinfunction "Q4_9") (pintype "output"))
    )
    (net (code "104") (name "/PV1") (class "Default")
      (node (ref "R11") (pin "2") (pinfunction "2_2") (pintype "passive"))
      (node (ref "R15") (pin "1") (pinfunction "1_1") (pintype "passive"))
      (node (ref "R16") (pin "1") (pinfunction "1_1") (pintype "passive"))
      (node (ref "U1") (pin "7") (pinfunction "VOUT_7") (pintype "output"))
      (node (ref "U12") (pin "2") (pinfunction "V1_2") (pintype "input"))
      (node (ref "U13") (pin "2") (pinfunction "V1_2") (pintype "input"))
      (node (ref "U14") (pin "2") (pinfunction "V1_2") (pintype "input"))
      (node (ref "U16") (pin "2") (pinfunction "V1_2") (pintype "input"))
      (node (ref "U18") (pin "2") (pinfunction "V1_2") (pintype "input"))
      (node (ref "U4") (pin "2") (pinfunction "V1_2") (pintype "input"))
      (node (ref "U5") (pin "2") (pinfunction "V1_2") (pintype "input"))
      (node (ref "U6") (pin "2") (pinfunction "V1_2") (pintype "input"))
    )
    (net (code "105") (name "/PV2") (class "Default")
      (node (ref "R10") (pin "1") (pinfunction "1_1") (pintype "passive"))
      (node (ref "R13") (pin "2") (pinfunction "2_2") (pintype "passive"))
      (node (ref "R18") (pin "1") (pinfunction "1_1") (pintype "passive"))
      (node (ref "U12") (pin "1") (pinfunction "V2_1") (pintype "input"))
      (node (ref "U13") (pin "1") (pinfunction "V2_1") (pintype "input"))
      (node (ref "U14") (pin "1") (pinfunction "V2_1") (pintype "input"))
      (node (ref "U16") (pin "1") (pinfunction "V2_1") (pintype "input"))
      (node (ref "U18") (pin "1") (pinfunction "V2_1") (pintype "input"))
      (node (ref "U2") (pin "7") (pinfunction "VOUT_7") (pintype "output"))
      (node (ref "U4") (pin "1") (pinfunction "V2_1") (pintype "input"))
      (node (ref "U5") (pin "1") (pinfunction "V2_1") (pintype "input"))
      (node (ref "U6") (pin "1") (pinfunction "V2_1") (pintype "input"))
    )
    (net (code "106") (name "/PV_D0") (class "Default")
      (node (ref "J1") (pin "9") (pinfunction "1_9") (pintype "passive"))
      (node (ref "U19") (pin "13") (pinfunction "DATA_IN_13") (pintype "input"))
    )
    (net (code "107") (name "/PV_D1") (class "Default")
      (node (ref "J1") (pin "10") (pinfunction "1_10") (pintype "passive"))
      (node (ref "U20") (pin "13") (pinfunction "DATA_IN_13") (pintype "input"))
    )
    (net (code "108") (name "/PV_VSEL0") (class "Default")
      (node (ref "J1") (pin "15") (pinfunction "1_15") (pintype "passive"))
      (node (ref "U19") (pin "1") (pinfunction "A_1") (pintype "input"))
      (node (ref "U20") (pin "1") (pinfunction "A_1") (pintype "input"))
    )
    (net (code "109") (name "/PV_VSEL1") (class "Default")
      (node (ref "J1") (pin "16") (pinfunction "1_16") (pintype "passive"))
      (node (ref "U19") (pin "2") (pinfunction "B_2") (pintype "input"))
      (node (ref "U20") (pin "2") (pinfunction "B_2") (pintype "input"))
    )
    (net (code "110") (name "/PV_VSEL2") (class "Default")
      (node (ref "J1") (pin "11") (pinfunction "1_11") (pintype "passive"))
      (node (ref "U19") (pin "3") (pinfunction "C_3") (pintype "input"))
      (node (ref "U20") (pin "3") (pinfunction "C_3") (pintype "input"))
    )
    (net (code "111") (name "/SD_CS") (class "Default")
      (node (ref "J1") (pin "55") (pinfunction "1_55") (pintype "passive"))
      (node (ref "U10") (pin "2") (pinfunction "CS_2") (pintype "bidirectional"))
    )
    (net (code "112") (name "/SD_VSEL0") (class "Default")
      (node (ref "U19") (pin "7") (pinfunction "Q3_7") (pintype "output"))
      (node (ref "U6") (pin "6") (pinfunction "S0_6") (pintype "input"))
    )
    (net (code "113") (name "/SD_VSEL1") (class "Default")
      (node (ref "U20") (pin "7") (pinfunction "Q3_7") (pintype "output"))
      (node (ref "U6") (pin "7") (pinfunction "S1_7") (pintype "input"))
    )
    (net (code "114") (name "/SPI5_MCLK") (class "Default")
      (node (ref "J2") (pin "6") (pinfunction "1_6") (pintype "passive"))
      (node (ref "U10") (pin "5") (pinfunction "CLK_5") (pintype "bidirectional"))
      (node (ref "U11") (pin "6") (pinfunction "CLK_6") (pintype "input"))
      (node (ref "U17") (pin "6") (pinfunction "CLK_6") (pintype "input"))
      (node (ref "U22") (pin "GND") (pinfunction "MCLK_GND") (pintype "bidirectional"))
      (node (ref "U23") (pin "GND") (pinfunction "MCLK_GND") (pintype "bidirectional"))
      (node (ref "U24") (pin "GND") (pinfunction "MCLK_GND") (pintype "bidirectional"))
      (node (ref "U9") (pin "6") (pinfunction "CLK_6") (pintype "input"))
    )
    (net (code "115") (name "/SPI5_MISO") (class "Default")
      (node (ref "J2") (pin "5") (pinfunction "1_5") (pintype "passive"))
      (node (ref "U10") (pin "7") (pinfunction "DO_7") (pintype "bidirectional"))
      (node (ref "U11") (pin "2") (pinfunction "SDO_2") (pintype "tri_state"))
      (node (ref "U17") (pin "2") (pinfunction "SDO_2") (pintype "tri_state"))
      (node (ref "U9") (pin "2") (pinfunction "SDO_2") (pintype "tri_state"))
    )
    (net (code "116") (name "/SPI5_MOSI") (class "Default")
      (node (ref "J2") (pin "8") (pinfunction "1_8") (pintype "passive"))
      (node (ref "U10") (pin "3") (pinfunction "DI_3") (pintype "bidirectional"))
      (node (ref "U11") (pin "5") (pinfunction "SDI_5") (pintype "input"))
      (node (ref "U17") (pin "5") (pinfunction "SDI_5") (pintype "input"))
      (node (ref "U22") (pin "MOSI") (pinfunction "MOSI_MOSI") (pintype "bidirectional"))
      (node (ref "U23") (pin "MOSI") (pinfunction "MOSI_MOSI") (pintype "bidirectional"))
      (node (ref "U24") (pin "MOSI") (pinfunction "MOSI_MOSI") (pintype "bidirectional"))
      (node (ref "U9") (pin "5") (pinfunction "SDI_5") (pintype "input"))
    )
    (net (code "117") (name "/SWD_TRACE") (class "Default")
      (node (ref "J1") (pin "28") (pinfunction "1_28") (pintype "passive"))
    )
    (net (code "118") (name "/TH_VSEL0") (class "Default")
      (node (ref "U19") (pin "10") (pinfunction "Q5_10") (pintype "output"))
      (node (ref "U4") (pin "6") (pinfunction "S0_6") (pintype "input"))
    )
    (net (code "119") (name "/TH_VSEL1") (class "Default")
      (node (ref "U20") (pin "10") (pinfunction "Q5_10") (pintype "output"))
      (node (ref "U4") (pin "7") (pinfunction "S1_7") (pintype "input"))
    )
    (net (code "120") (name "/TP_INT1") (class "Default")
      (node (ref "J1") (pin "46") (pinfunction "1_46") (pintype "passive"))
    )
    (net (code "121") (name "/UART5_RX") (class "Default")
      (node (ref "J1") (pin "40") (pinfunction "1_40") (pintype "passive"))
      (node (ref "U26") (pin "6") (pinfunction "TXD_6") (pintype "bidirectional"))
    )
    (net (code "122") (name "/UART5_TX") (class "Default")
      (node (ref "J1") (pin "43") (pinfunction "1_43") (pintype "passive"))
      (node (ref "U26") (pin "8") (pinfunction "RXD_8") (pintype "bidirectional"))
    )
    (net (code "123") (name "/USART1_RX") (class "Default")
      (node (ref "J1") (pin "51") (pinfunction "1_51") (pintype "passive"))
      (node (ref "U25") (pin "16") (pinfunction "TXD_16") (pintype "output"))
    )
    (net (code "124") (name "/USART1_TX") (class "Default")
      (node (ref "J1") (pin "52") (pinfunction "1_52") (pintype "passive"))
      (node (ref "U25") (pin "15") (pinfunction "RXD_15") (pintype "input"))
    )
    (net (code "125") (name "/VADJ1") (class "Default")
      (node (ref "U1") (pin "2") (pinfunction "VADJ_2") (pintype "input"))
      (node (ref "U3") (pin "1") (pinfunction "OUT_1") (pintype "bidirectional"))
      (node (ref "U3") (pin "2") (pinfunction "-IN_2") (pintype "bidirectional"))
    )
    (net (code "126") (name "/VADJ1_0") (class "Default")
      (node (ref "J1") (pin "25") (pinfunction "1_25") (pintype "passive"))
      (node (ref "R3") (pin "2") (pinfunction "2_2") (pintype "passive"))
    )
    (net (code "127") (name "/VADJ1_1") (class "Default")
      (node (ref "J1") (pin "24") (pinfunction "1_24") (pintype "passive"))
      (node (ref "R2") (pin "2") (pinfunction "2_2") (pintype "passive"))
    )
    (net (code "128") (name "/VADJ2") (class "Default")
      (node (ref "U2") (pin "2") (pinfunction "VADJ_2") (pintype "input"))
      (node (ref "U3") (pin "6") (pinfunction "-IN_6") (pintype "bidirectional"))
      (node (ref "U3") (pin "7") (pinfunction "OUT_7") (pintype "bidirectional"))
    )
    (net (code "129") (name "/VAF") (class "Default")
      (node (ref "C8") (pin "1") (pinfunction "1_1") (pintype "passive"))
      (node (ref "U17") (pin "3") (pinfunction "~{WP}_3") (pintype "bidirectional"))
      (node (ref "U17") (pin "7") (pinfunction "~{HLD}_7") (pintype "bidirectional"))
      (node (ref "U17") (pin "8") (pinfunction "VCC_8") (pintype "power_in"))
      (node (ref "U18") (pin "8") (pinfunction "VOUT_8") (pintype "output"))
    )
    (net (code "130") (name "/VDD") (class "Default")
      (node (ref "J1") (pin "22") (pinfunction "1_22") (pintype "passive"))
    )
    (net (code "131") (name "/VEE") (class "Default")
      (node (ref "C2") (pin "1") (pinfunction "1_1") (pintype "passive"))
      (node (ref "U5") (pin "8") (pinfunction "VOUT_8") (pintype "output"))
      (node (ref "U9") (pin "3") (pinfunction "~{WP}_3") (pintype "bidirectional"))
      (node (ref "U9") (pin "7") (pinfunction "~{HLD}_7") (pintype "bidirectional"))
      (node (ref "U9") (pin "8") (pinfunction "VCC_8") (pintype "power_in"))
    )
    (net (code "132") (name "/VOF") (class "Default")
      (node (ref "C5") (pin "1") (pinfunction "1_1") (pintype "passive"))
      (node (ref "U11") (pin "3") (pinfunction "~{WP}_3") (pintype "bidirectional"))
      (node (ref "U11") (pin "7") (pinfunction "~{HLD}_7") (pintype "bidirectional"))
      (node (ref "U11") (pin "8") (pinfunction "VCC_8") (pintype "power_in"))
      (node (ref "U16") (pin "8") (pinfunction "VOUT_8") (pintype "output"))
    )
    (net (code "133") (name "/VSD") (class "Default")
      (node (ref "C1") (pin "1") (pinfunction "1_1") (pintype "passive"))
      (node (ref "C16") (pin "1") (pinfunction "1_1") (pintype "passive"))
      (node (ref "U10") (pin "4") (pinfunction "VCC_4") (pintype "passive"))
      (node (ref "U6") (pin "8") (pinfunction "VOUT_8") (pintype "output"))
    )
    (net (code "134") (name "/VTH") (class "Default")
      (node (ref "C21") (pin "1") (pinfunction "1_1") (pintype "passive"))
      (node (ref "U4") (pin "8") (pinfunction "VOUT_8") (pintype "output"))
      (node (ref "U8") (pin "8") (pinfunction "VDD_8") (pintype "bidirectional"))
    )
    (net (code "135") (name "/WF_VSEL0") (class "Default")
      (node (ref "U12") (pin "6") (pinfunction "S0_6") (pintype "input"))
      (node (ref "U19") (pin "11") (pinfunction "Q6_11") (pintype "output"))
    )
    (net (code "136") (name "/WF_VSEL1") (class "Default")
      (node (ref "U12") (pin "7") (pinfunction "S1_7") (pintype "input"))
      (node (ref "U20") (pin "11") (pinfunction "Q6_11") (pintype "output"))
    )
    (net (code "137") (name "/~{BT_RESET}") (class "Default")
      (node (ref "J1") (pin "44") (pinfunction "1_44") (pintype "passive"))
      (node (ref "TP14") (pin "TP") (pinfunction "TP_TP") (pintype "input"))
      (node (ref "U26") (pin "3") (pinfunction "~{RESET}_3") (pintype "bidirectional"))
    )
    (net (code "138") (name "/~{PLR0_CS}") (class "Default")
      (node (ref "J2") (pin "49") (pinfunction "1_49") (pintype "passive"))
      (node (ref "U22") (pin "!CLR") (pinfunction "~{CS}_!CLR") (pintype "bidirectional"))
    )
    (net (code "139") (name "/~{PLR1_CS}") (class "Default")
      (node (ref "J2") (pin "52") (pinfunction "1_52") (pintype "passive"))
      (node (ref "U23") (pin "!CLR") (pinfunction "~{CS}_!CLR") (pintype "bidirectional"))
    )
    (net (code "140") (name "/~{PLR2_CS}") (class "Default")
      (node (ref "J2") (pin "51") (pinfunction "1_51") (pintype "passive"))
      (node (ref "U24") (pin "!CLR") (pinfunction "~{CS}_!CLR") (pintype "bidirectional"))
    )
    (net (code "141") (name "/~{PLR_CLR}") (class "Default")
      (node (ref "J2") (pin "50") (pinfunction "1_50") (pintype "passive"))
      (node (ref "U22") (pin "!CS") (pinfunction "~{CLR}_!CS") (pintype "bidirectional"))
      (node (ref "U23") (pin "!CS") (pinfunction "~{CLR}_!CS") (pintype "bidirectional"))
      (node (ref "U24") (pin "!CS") (pinfunction "~{CLR}_!CS") (pintype "bidirectional"))
    )
    (net (code "142") (name "/~{PV_CLR}") (class "Default")
      (node (ref "J1") (pin "13") (pinfunction "1_13") (pintype "passive"))
      (node (ref "R8") (pin "2") (pinfunction "2_2") (pintype "passive"))
      (node (ref "U19") (pin "15") (pinfunction "CLEAR_15") (pintype "input"))
      (node (ref "U20") (pin "15") (pinfunction "CLEAR_15") (pintype "input"))
    )
    (net (code "143") (name "/~{PV_EN}") (class "Default")
      (node (ref "J1") (pin "14") (pinfunction "1_14") (pintype "passive"))
      (node (ref "R9") (pin "1") (pinfunction "1_1") (pintype "passive"))
      (node (ref "U19") (pin "14") (pinfunction "ENABLE_14") (pintype "input"))
      (node (ref "U20") (pin "14") (pinfunction "ENABLE_14") (pintype "input"))
    )
    (net (code "144") (name "/~{USB_RST}") (class "Default")
      (node (ref "J2") (pin "30") (pinfunction "1_30") (pintype "passive"))
      (node (ref "U27") (pin "!RST") (pinfunction "~{RST}_!RST") (pintype "bidirectional"))
      (node (ref "U27") (pin "PU1") (pinfunction "PU1_PU1") (pintype "bidirectional"))
    )
    (net (code "145") (name "/~{WF_RESET}") (class "Default")
      (node (ref "J1") (pin "12") (pinfunction "1_12") (pintype "passive"))
      (node (ref "U25") (pin "1") (pinfunction "RESET_1") (pintype "input"))
    )
    (net (code "146") (name "GND") (class "Default")
      (node (ref "C1") (pin "2") (pinfunction "2_2") (pintype "passive"))
      (node (ref "C10") (pin "2") (pinfunction "2_2") (pintype "passive"))
      (node (ref "C11") (pin "2") (pinfunction "2_2") (pintype "passive"))
      (node (ref "C12") (pin "2") (pinfunction "2_2") (pintype "passive"))
      (node (ref "C14") (pin "2") (pinfunction "2_2") (pintype "passive"))
      (node (ref "C16") (pin "2") (pinfunction "2_2") (pintype "passive"))
      (node (ref "C17") (pin "2") (pinfunction "2_2") (pintype "passive"))
      (node (ref "C18") (pin "2") (pinfunction "2_2") (pintype "passive"))
      (node (ref "C19") (pin "2") (pinfunction "2_2") (pintype "passive"))
      (node (ref "C20") (pin "2") (pinfunction "2_2") (pintype "passive"))
      (node (ref "C22") (pin "2") (pinfunction "2_2") (pintype "passive"))
      (node (ref "C4") (pin "2") (pinfunction "2_2") (pintype "passive"))
      (node (ref "C9") (pin "2") (pinfunction "2_2") (pintype "passive"))
      (node (ref "J1") (pin "63") (pinfunction "1_63") (pintype "passive"))
      (node (ref "J1") (pin "64") (pinfunction "1_64") (pintype "passive"))
      (node (ref "J2") (pin "11") (pinfunction "1_11") (pintype "passive"))
      (node (ref "J2") (pin "29") (pinfunction "1_29") (pintype "passive"))
      (node (ref "J2") (pin "63") (pinfunction "1_63") (pintype "passive"))
      (node (ref "J2") (pin "64") (pinfunction "1_64") (pintype "passive"))
      (node (ref "R1") (pin "1") (pinfunction "1_1") (pintype "passive"))
      (node (ref "R12") (pin "1") (pinfunction "1_1") (pintype "passive"))
      (node (ref "R14") (pin "1") (pinfunction "1_1") (pintype "passive"))
      (node (ref "R6") (pin "1") (pinfunction "1_1") (pintype "passive"))
      (node (ref "R8") (pin "1") (pinfunction "1_1") (pintype "passive"))
      (node (ref "U1") (pin "4") (pinfunction "GND_4") (pintype "power_in"))
      (node (ref "U1") (pin "6") (pinfunction "GND_6") (pintype "power_in"))
      (node (ref "U10") (pin "6") (pinfunction "GND_6") (pintype "power_in"))
      (node (ref "U12") (pin "4") (pinfunction "GND_4") (pintype "power_in"))
      (node (ref "U13") (pin "4") (pinfunction "GND_4") (pintype "power_in"))
      (node (ref "U14") (pin "4") (pinfunction "GND_4") (pintype "power_in"))
      (node (ref "U16") (pin "4") (pinfunction "GND_4") (pintype "power_in"))
      (node (ref "U18") (pin "4") (pinfunction "GND_4") (pintype "power_in"))
      (node (ref "U19") (pin "8") (pinfunction "GND_8") (pintype "passive"))
      (node (ref "U2") (pin "4") (pinfunction "GND_4") (pintype "power_in"))
      (node (ref "U2") (pin "6") (pinfunction "GND_6") (pintype "power_in"))
      (node (ref "U20") (pin "8") (pinfunction "GND_8") (pintype "passive"))
      (node (ref "U21") (pin "8") (pinfunction "+V_8") (pintype "bidirectional"))
      (node (ref "U22") (pin "CHA") (pinfunction "GND_CHA") (pintype "power_in"))
      (node (ref "U23") (pin "CHA") (pinfunction "GND_CHA") (pintype "power_in"))
      (node (ref "U24") (pin "CHA") (pinfunction "GND_CHA") (pintype "power_in"))
      (node (ref "U27") (pin "GND-0") (pinfunction "GND_GND-0") (pintype "power_in"))
      (node (ref "U27") (pin "GND-1") (pinfunction "GND_GND-1") (pintype "power_in"))
      (node (ref "U27") (pin "SLD") (pinfunction "GND_SLD") (pintype "power_in"))
      (node (ref "U3") (pin "8") (pinfunction "+V_8") (pintype "bidirectional"))
      (node (ref "U4") (pin "4") (pinfunction "GND_4") (pintype "power_in"))
      (node (ref "U5") (pin "4") (pinfunction "GND_4") (pintype "power_in"))
      (node (ref "U6") (pin "4") (pinfunction "GND_4") (pintype "power_in"))
      (node (ref "U6") (pin "5") (pinfunction "DGND_5") (pintype "output"))
      (node (ref "U7") (pin "2") (pinfunction "V-_2") (pintype "power_in"))
    )
    (net (code "147") (name "Net-(C22-Pad1)") (class "Default")
      (node (ref "C22") (pin "1") (pinfunction "1_1") (pintype "passive"))
      (node (ref "LED1") (pin "A") (pinfunction "A_A") (pintype "passive"))
      (node (ref "R4") (pin "1") (pinfunction "1_1") (pintype "passive"))
    )
    (net (code "148") (name "Net-(U3A-+IN)") (class "Default")
      (node (ref "R1") (pin "2") (pinfunction "2_2") (pintype "passive"))
      (node (ref "R2") (pin "1") (pinfunction "1_1") (pintype "passive"))
      (node (ref "R3") (pin "1") (pinfunction "1_1") (pintype "passive"))
      (node (ref "U3") (pin "3") (pinfunction "+IN_3") (pintype "bidirectional"))
    )
    (net (code "149") (name "Net-(U4-DGND)") (class "Default")
      (node (ref "C21") (pin "2") (pinfunction "2_2") (pintype "passive"))
      (node (ref "C3") (pin "2") (pinfunction "2_2") (pintype "passive"))
      (node (ref "U4") (pin "5") (pinfunction "DGND_5") (pintype "output"))
      (node (ref "U8") (pin "2") (pinfunction "VSS_2") (pintype "bidirectional"))
    )
    (net (code "150") (name "Net-(U5-DGND)") (class "Default")
      (node (ref "C2") (pin "2") (pinfunction "2_2") (pintype "passive"))
      (node (ref "U5") (pin "5") (pinfunction "DGND_5") (pintype "output"))
      (node (ref "U9") (pin "4") (pinfunction "GND_4") (pintype "power_in"))
    )
    (net (code "151") (name "Net-(U8-VCORE)") (class "Default")
      (node (ref "C3") (pin "1") (pinfunction "1_1") (pintype "passive"))
      (node (ref "U8") (pin "1") (pinfunction "VCORE_1") (pintype "bidirectional"))
    )
    (net (code "152") (name "Net-(U11-GND)") (class "Default")
      (node (ref "C5") (pin "2") (pinfunction "2_2") (pintype "passive"))
      (node (ref "U11") (pin "4") (pinfunction "GND_4") (pintype "power_in"))
      (node (ref "U16") (pin "5") (pinfunction "DGND_5") (pintype "output"))
    )
    (net (code "153") (name "Net-(U12-DGND)") (class "Default")
      (node (ref "C15") (pin "2") (pinfunction "2_2") (pintype "passive"))
      (node (ref "C6") (pin "2") (pinfunction "2_2") (pintype "passive"))
      (node (ref "U12") (pin "5") (pinfunction "DGND_5") (pintype "output"))
      (node (ref "U25") (pin "9") (pinfunction "GND_9") (pintype "power_in"))
    )
    (net (code "154") (name "Net-(U12-VOUT)") (class "Default")
      (node (ref "C15") (pin "1") (pinfunction "1_1") (pintype "passive"))
      (node (ref "C6") (pin "1") (pinfunction "1_1") (pintype "passive"))
      (node (ref "U12") (pin "8") (pinfunction "VOUT_8") (pintype "output"))
      (node (ref "U25") (pin "8") (pinfunction "VCC_8") (pintype "power_in"))
    )
    (net (code "155") (name "Net-(U13-DGND)") (class "Default")
      (node (ref "U13") (pin "5") (pinfunction "DGND_5") (pintype "output"))
      (node (ref "U26") (pin "23") (pinfunction "GND_23") (pintype "bidirectional"))
    )
    (net (code "156") (name "Net-(U13-VOUT)") (class "Default")
      (node (ref "U13") (pin "8") (pinfunction "VOUT_8") (pintype "output"))
      (node (ref "U26") (pin "24") (pinfunction "VIN_24") (pintype "bidirectional"))
    )
    (net (code "157") (name "Net-(U14-DGND)") (class "Default")
      (node (ref "C13") (pin "2") (pinfunction "2_2") (pintype "passive"))
      (node (ref "C7") (pin "2") (pinfunction "2_2") (pintype "passive"))
      (node (ref "U14") (pin "5") (pinfunction "DGND_5") (pintype "output"))
      (node (ref "U15") (pin "8") (pinfunction "GND_8") (pintype "power_in"))
    )
    (net (code "158") (name "Net-(U14-VOUT)") (class "Default")
      (node (ref "C13") (pin "1") (pinfunction "1_1") (pintype "passive"))
      (node (ref "C7") (pin "1") (pinfunction "1_1") (pintype "passive"))
      (node (ref "U14") (pin "8") (pinfunction "VOUT_8") (pintype "output"))
      (node (ref "U15") (pin "3") (pinfunction "VDD_3") (pintype "power_in"))
    )
    (net (code "159") (name "Net-(U15-LED1)") (class "Default")
      (node (ref "LED1") (pin "C") (pinfunction "C_C") (pintype "passive"))
      (node (ref "U15") (pin "9") (pinfunction "LED1_9") (pintype "output"))
    )
    (net (code "160") (name "Net-(U17-GND)") (class "Default")
      (node (ref "C8") (pin "2") (pinfunction "2_2") (pintype "passive"))
      (node (ref "U17") (pin "4") (pinfunction "GND_4") (pintype "power_in"))
      (node (ref "U18") (pin "5") (pinfunction "DGND_5") (pintype "output"))
    )
    (net (code "161") (name "Net-(U21A-+IN)") (class "Default")
      (node (ref "R11") (pin "1") (pinfunction "1_1") (pintype "passive"))
      (node (ref "R12") (pin "2") (pinfunction "2_2") (pintype "passive"))
      (node (ref "U21") (pin "3") (pinfunction "+IN_3") (pintype "bidirectional"))
    )
    (net (code "162") (name "Net-(U21B-+IN)") (class "Default")
      (node (ref "R13") (pin "1") (pinfunction "1_1") (pintype "passive"))
      (node (ref "R14") (pin "2") (pinfunction "2_2") (pintype "passive"))
      (node (ref "U21") (pin "5") (pinfunction "+IN_5") (pintype "bidirectional"))
    )
    (net (code "163") (name "Net-(U22-CHA)") (class "Default")
      (node (ref "R17") (pin "2") (pinfunction "2_2") (pintype "passive"))
      (node (ref "U22") (pin "CHB") (pinfunction "CHA_CHB") (pintype "power_in"))
    )
    (net (code "164") (name "Net-(U22-CHB)") (class "Default")
      (node (ref "R19") (pin "2") (pinfunction "2_2") (pintype "passive"))
      (node (ref "U22") (pin "MCLK") (pinfunction "CHB_MCLK") (pintype "bidirectional"))
    )
    (net (code "165") (name "Net-(U23-CHA)") (class "Default")
      (node (ref "R15") (pin "2") (pinfunction "2_2") (pintype "passive"))
      (node (ref "U23") (pin "CHB") (pinfunction "CHA_CHB") (pintype "power_in"))
    )
    (net (code "166") (name "Net-(U23-CHB)") (class "Default")
      (node (ref "R16") (pin "2") (pinfunction "2_2") (pintype "passive"))
      (node (ref "U23") (pin "MCLK") (pinfunction "CHB_MCLK") (pintype "bidirectional"))
    )
    (net (code "167") (name "Net-(U24-CHA)") (class "Default")
      (node (ref "R18") (pin "2") (pinfunction "2_2") (pintype "passive"))
      (node (ref "U24") (pin "CHB") (pinfunction "CHA_CHB") (pintype "power_in"))
    )
    (net (code "168") (name "Net-(U24-CHB)") (class "Default")
      (node (ref "R10") (pin "2") (pinfunction "2_2") (pintype "passive"))
      (node (ref "U24") (pin "MCLK") (pinfunction "CHB_MCLK") (pintype "bidirectional"))
    )
    (net (code "169") (name "Net-(U25-ADC)") (class "Default")
      (node (ref "TP1") (pin "TP") (pinfunction "TP_TP") (pintype "input"))
      (node (ref "U25") (pin "2") (pinfunction "ADC_2") (pintype "passive"))
    )
    (net (code "170") (name "Net-(U25-CH_PD)") (class "Default")
      (node (ref "TP2") (pin "TP") (pinfunction "TP_TP") (pintype "input"))
      (node (ref "U25") (pin "3") (pinfunction "CH_PD_3") (pintype "input"))
    )
    (net (code "171") (name "Net-(U25-GPIO0)") (class "Default")
      (node (ref "TP9") (pin "TP") (pinfunction "TP_TP") (pintype "input"))
      (node (ref "U25") (pin "12") (pinfunction "GPIO0_12") (pintype "bidirectional"))
    )
    (net (code "172") (name "Net-(U25-GPIO2)") (class "Default")
      (node (ref "TP8") (pin "TP") (pinfunction "TP_TP") (pintype "input"))
      (node (ref "U25") (pin "11") (pinfunction "GPIO2_11") (pintype "bidirectional"))
    )
    (net (code "173") (name "Net-(U25-GPIO4)") (class "Default")
      (node (ref "TP11") (pin "TP") (pinfunction "TP_TP") (pintype "input"))
      (node (ref "U25") (pin "14") (pinfunction "GPIO4_14") (pintype "bidirectional"))
    )
    (net (code "174") (name "Net-(U25-GPIO5)") (class "Default")
      (node (ref "TP10") (pin "TP") (pinfunction "TP_TP") (pintype "input"))
      (node (ref "U25") (pin "13") (pinfunction "GPIO5_13") (pintype "bidirectional"))
    )
    (net (code "175") (name "Net-(U25-GPIO12)") (class "Default")
      (node (ref "TP5") (pin "TP") (pinfunction "TP_TP") (pintype "input"))
      (node (ref "U25") (pin "6") (pinfunction "GPIO12_6") (pintype "bidirectional"))
    )
    (net (code "176") (name "Net-(U25-GPIO13)") (class "Default")
      (node (ref "TP6") (pin "TP") (pinfunction "TP_TP") (pintype "input"))
      (node (ref "U25") (pin "7") (pinfunction "GPIO13_7") (pintype "bidirectional"))
    )
    (net (code "177") (name "Net-(U25-GPIO14)") (class "Default")
      (node (ref "TP4") (pin "TP") (pinfunction "TP_TP") (pintype "input"))
      (node (ref "U25") (pin "5") (pinfunction "GPIO14_5") (pintype "bidirectional"))
    )
    (net (code "178") (name "Net-(U25-GPIO15)") (class "Default")
      (node (ref "TP7") (pin "TP") (pinfunction "TP_TP") (pintype "input"))
      (node (ref "U25") (pin "10") (pinfunction "GPIO15_10") (pintype "bidirectional"))
    )
    (net (code "179") (name "Net-(U25-GPIO16)") (class "Default")
      (node (ref "TP3") (pin "TP") (pinfunction "TP_TP") (pintype "input"))
      (node (ref "U25") (pin "4") (pinfunction "GPIO16_4") (pintype "bidirectional"))
    )
    (net (code "180") (name "Net-(U26-BOOT0)") (class "Default")
      (node (ref "TP13") (pin "TP") (pinfunction "TP_TP") (pintype "input"))
      (node (ref "U26") (pin "2") (pinfunction "BOOT0_2") (pintype "bidirectional"))
    )
    (net (code "181") (name "Net-(U26-CTS)") (class "Default")
      (node (ref "TP20") (pin "TP") (pinfunction "TP_TP") (pintype "input"))
      (node (ref "U26") (pin "9") (pinfunction "CTS_9") (pintype "bidirectional"))
    )
    (net (code "182") (name "Net-(U26-GPIO[0])") (class "Default")
      (node (ref "TP25") (pin "TP") (pinfunction "TP_TP") (pintype "input"))
      (node (ref "U26") (pin "16") (pinfunction "GPIO[0]_16") (pintype "bidirectional"))
    )
    (net (code "183") (name "Net-(U26-GPIO[1])") (class "Default")
      (node (ref "TP26") (pin "TP") (pinfunction "TP_TP") (pintype "input"))
      (node (ref "U26") (pin "17") (pinfunction "GPIO[1]_17") (pintype "bidirectional"))
    )
    (net (code "184") (name "Net-(U26-GPIO[2])") (class "Default")
      (node (ref "TP28") (pin "TP") (pinfunction "TP_TP") (pintype "input"))
      (node (ref "U26") (pin "19") (pinfunction "GPIO[2]_19") (pintype "bidirectional"))
    )
    (net (code "185") (name "Net-(U26-GPIO[3])") (class "Default")
      (node (ref "TP12") (pin "TP") (pinfunction "TP_TP") (pintype "input"))
      (node (ref "U26") (pin "1") (pinfunction "GPIO[3]_1") (pintype "bidirectional"))
    )
    (net (code "186") (name "Net-(U26-GPIO[4])") (class "Default")
      (node (ref "TP27") (pin "TP") (pinfunction "TP_TP") (pintype "input"))
      (node (ref "U26") (pin "18") (pinfunction "GPIO[4]_18") (pintype "bidirectional"))
    )
    (net (code "187") (name "Net-(U26-GPIO[5])") (class "Default")
      (node (ref "TP29") (pin "TP") (pinfunction "TP_TP") (pintype "input"))
      (node (ref "U26") (pin "20") (pinfunction "GPIO[5]_20") (pintype "bidirectional"))
    )
    (net (code "188") (name "Net-(U26-GPIO[6])") (class "Default")
      (node (ref "TP31") (pin "TP") (pinfunction "TP_TP") (pintype "input"))
      (node (ref "U26") (pin "22") (pinfunction "GPIO[6]_22") (pintype "bidirectional"))
    )
    (net (code "189") (name "Net-(U26-GPIO[7])") (class "Default")
      (node (ref "TP22") (pin "TP") (pinfunction "TP_TP") (pintype "input"))
      (node (ref "U26") (pin "13") (pinfunction "GPIO[7]_13") (pintype "bidirectional"))
    )
    (net (code "190") (name "Net-(U26-GPIO[8])") (class "Default")
      (node (ref "TP15") (pin "TP") (pinfunction "TP_TP") (pintype "input"))
      (node (ref "U26") (pin "4") (pinfunction "GPIO[8]_4") (pintype "bidirectional"))
    )
    (net (code "191") (name "Net-(U26-GPIO[9])") (class "Default")
      (node (ref "TP17") (pin "TP") (pinfunction "TP_TP") (pintype "input"))
      (node (ref "U26") (pin "7") (pinfunction "GPIO[9]_7") (pintype "bidirectional"))
    )
    (net (code "192") (name "Net-(U26-GPIO[10])") (class "Default")
      (node (ref "TP16") (pin "TP") (pinfunction "TP_TP") (pintype "input"))
      (node (ref "U26") (pin "5") (pinfunction "GPIO[10]_5") (pintype "bidirectional"))
    )
    (net (code "193") (name "Net-(U26-GPIO[11])") (class "Default")
      (node (ref "TP18") (pin "TP") (pinfunction "TP_TP") (pintype "input"))
      (node (ref "U26") (pin "11") (pinfunction "GPIO[11]_11") (pintype "bidirectional"))
    )
    (net (code "194") (name "Net-(U26-GPIO[12])") (class "Default")
      (node (ref "TP19") (pin "TP") (pinfunction "TP_TP") (pintype "input"))
      (node (ref "U26") (pin "12") (pinfunction "GPIO[12]_12") (pintype "bidirectional"))
    )
    (net (code "195") (name "Net-(U26-GPIO[13])") (class "Default")
      (node (ref "TP24") (pin "TP") (pinfunction "TP_TP") (pintype "input"))
      (node (ref "U26") (pin "15") (pinfunction "GPIO[13]_15") (pintype "bidirectional"))
    )
    (net (code "196") (name "Net-(U26-GPIO[14])") (class "Default")
      (node (ref "TP23") (pin "TP") (pinfunction "TP_TP") (pintype "input"))
      (node (ref "U26") (pin "14") (pinfunction "GPIO[14]_14") (pintype "bidirectional"))
    )
    (net (code "197") (name "Net-(U26-GPIO[15])") (class "Default")
      (node (ref "TP30") (pin "TP") (pinfunction "TP_TP") (pintype "input"))
      (node (ref "U26") (pin "21") (pinfunction "GPIO[15]_21") (pintype "bidirectional"))
    )
    (net (code "198") (name "Net-(U26-RTS)") (class "Default")
      (node (ref "TP21") (pin "TP") (pinfunction "TP_TP") (pintype "input"))
      (node (ref "U26") (pin "10") (pinfunction "RTS_10") (pintype "bidirectional"))
    )
    (net (code "199") (name "Net-(U27-VUSB)") (class "Default")
      (node (ref "U27") (pin "PU2") (pinfunction "PU2_PU2") (pintype "bidirectional"))
      (node (ref "U27") (pin "USB") (pinfunction "VUSB_USB") (pintype "output"))
    )
    (net (code "200") (name "unconnected-(J2AH-1-Pad4)") (class "Default")
      (node (ref "J2") (pin "4") (pinfunction "1_4") (pintype "passive"))
    )
    (net (code "201") (name "unconnected-(U8-AL_H{slash}MISO-Pad5)") (class "Default")
      (node (ref "U8") (pin "5") (pinfunction "AL_H/MISO_5") (pintype "bidirectional"))
    )
    (net (code "202") (name "unconnected-(U8-AL_L-Pad6)") (class "Default")
      (node (ref "U8") (pin "6") (pinfunction "AL_L_6") (pintype "bidirectional"))
    )
    (net (code "203") (name "unconnected-(U8-NC-Pad7)") (class "Default")
      (node (ref "U8") (pin "7") (pinfunction "NC_7") (pintype "bidirectional"))
    )
    (net (code "204") (name "unconnected-(U15-INT-Pad4)") (class "Default")
      (node (ref "U15") (pin "4") (pinfunction "INT_4") (pintype "passive"))
    )
    (net (code "205") (name "unconnected-(U15-LED2-Pad6)") (class "Default")
      (node (ref "U15") (pin "6") (pinfunction "LED2_6") (pintype "output"))
    )
    (net (code "206") (name "unconnected-(U15-LED3-Pad7)") (class "Default")
      (node (ref "U15") (pin "7") (pinfunction "LED3_7") (pintype "output"))
    )
    (net (code "207") (name "unconnected-(U27-PadAC4)") (class "Default")
      (node (ref "U27") (pin "AC4") (pinfunction "AC4_AC4") (pintype "bidirectional"))
    )
    (net (code "208") (name "unconnected-(U27-PadAC5)") (class "Default")
      (node (ref "U27") (pin "AC5") (pinfunction "AC5_AC5") (pintype "bidirectional"))
    )
    (net (code "209") (name "unconnected-(U27-PadAC6)") (class "Default")
      (node (ref "U27") (pin "AC6") (pinfunction "AC6_AC6") (pintype "bidirectional"))
    )
    (net (code "210") (name "unconnected-(U27-PadAC7)") (class "Default")
      (node (ref "U27") (pin "AC7") (pinfunction "AC7_AC7") (pintype "bidirectional"))
    )
    (net (code "211") (name "unconnected-(U27-PadAC8)") (class "Default")
      (node (ref "U27") (pin "AC8") (pinfunction "AC8_AC8") (pintype "bidirectional"))
    )
    (net (code "212") (name "unconnected-(U27-PadAC9)") (class "Default")
      (node (ref "U27") (pin "AC9") (pinfunction "AC9_AC9") (pintype "bidirectional"))
    )
  )
)
